# Mid.net
KiCad netlist of a schematic drawn in Altium Designer
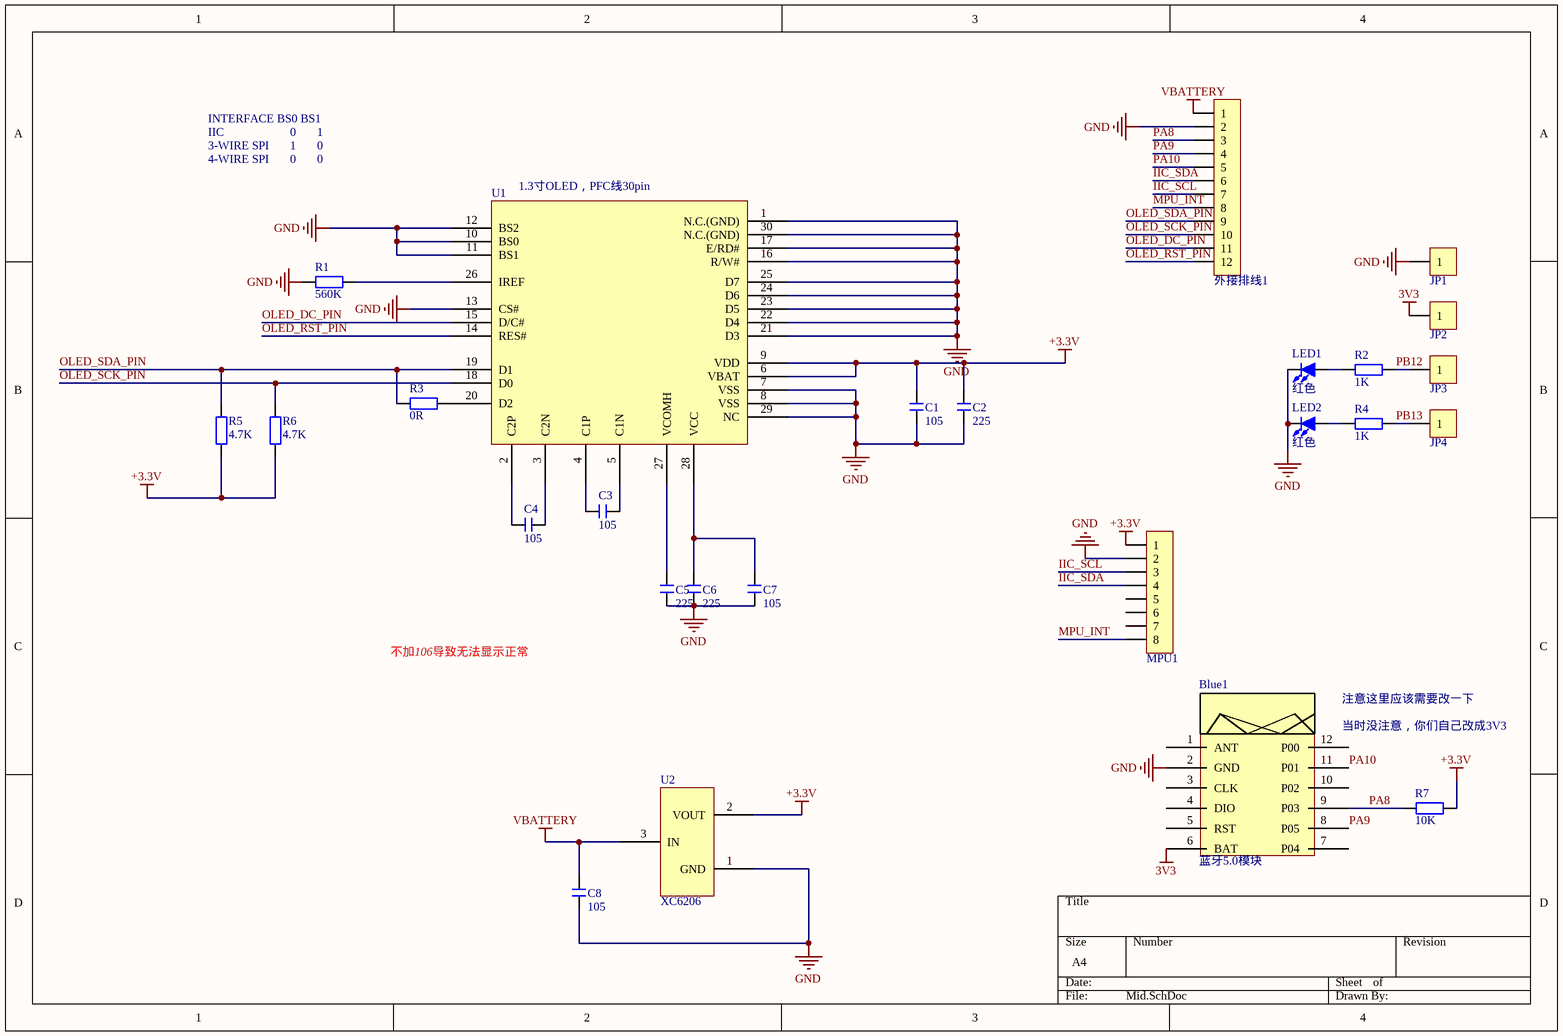
[diagram p0: Mid.SchDoc]

(export (version "E")
  (design (tool "Eeschema 10.0.6"))
  (components
    (comp (ref "Blue1") (value "蓝牙5.0模块") (footprint "PW02") (libsource (lib "未分类器件") (part "PW02")))
    (comp (ref "C1")
      (value "105")
      (footprint "C 0805")
      (description "无极性贴片电容")
      (fields (field (name "版权归属") "源创客"))
      (libsource (lib "电阻-电容-电感") (part "C"))
    )
    (comp (ref "C2")
      (value "225")
      (footprint "C 0805")
      (description "无极性贴片电容")
      (fields (field (name "版权归属") "源创客"))
      (libsource (lib "电阻-电容-电感") (part "C"))
    )
    (comp (ref "C3")
      (value "105")
      (footprint "C 0805")
      (description "无极性贴片电容")
      (fields (field (name "版权归属") "源创客"))
      (libsource (lib "电阻-电容-电感") (part "C"))
    )
    (comp (ref "C4")
      (value "105")
      (footprint "C 0805")
      (description "无极性贴片电容")
      (fields (field (name "版权归属") "源创客"))
      (libsource (lib "电阻-电容-电感") (part "C"))
    )
    (comp (ref "C5")
      (value "225")
      (footprint "C 0805")
      (description "无极性贴片电容")
      (fields (field (name "版权归属") "源创客"))
      (libsource (lib "电阻-电容-电感") (part "C"))
    )
    (comp (ref "C6")
      (value "225")
      (footprint "C 0805")
      (description "无极性贴片电容")
      (fields (field (name "版权归属") "源创客"))
      (libsource (lib "电阻-电容-电感") (part "C"))
    )
    (comp (ref "C7")
      (value "105")
      (footprint "C 0805")
      (description "无极性贴片电容")
      (fields (field (name "版权归属") "源创客"))
      (libsource (lib "电阻-电容-电感") (part "C"))
    )
    (comp (ref "C8")
      (value "105")
      (footprint "C 0805")
      (description "无极性贴片电容")
      (fields (field (name "版权归属") "源创客"))
      (libsource (lib "电阻-电容-电感") (part "C"))
    )
    (comp (ref "JP1")
      (value "HDR-1X1")
      (footprint "HDR-1X1")
      (description "1P接插件")
      (fields (field (name "版权归属") "源创客"))
      (libsource (lib "接插件") (part "Header 1"))
    )
    (comp (ref "JP2")
      (value "HDR-1X1")
      (footprint "HDR-1X1")
      (description "1P接插件")
      (fields (field (name "版权归属") "源创客"))
      (libsource (lib "接插件") (part "Header 1"))
    )
    (comp (ref "JP3")
      (value "HDR-1X1")
      (footprint "HDR-1X1")
      (description "1P接插件")
      (fields (field (name "版权归属") "源创客"))
      (libsource (lib "接插件") (part "Header 1"))
    )
    (comp (ref "JP4")
      (value "HDR-1X1")
      (footprint "HDR-1X1")
      (description "1P接插件")
      (fields (field (name "版权归属") "源创客"))
      (libsource (lib "接插件") (part "Header 1"))
    )
    (comp (ref "LED1")
      (value "红色")
      (footprint "LED 0805B")
      (description "贴片LED")
      (fields (field (name "版权归属") "源创客"))
      (libsource (lib "LED") (part "LED-SMD"))
    )
    (comp (ref "LED2")
      (value "红色")
      (footprint "LED 0805G")
      (description "贴片LED")
      (fields (field (name "版权归属") "源创客"))
      (libsource (lib "LED") (part "LED-SMD"))
    )
    (comp (ref "MPU1")
      (value "HDR-1X8")
      (footprint "HDR-1X8")
      (description "8P接插件")
      (fields (field (name "版权归属") "源创客"))
      (libsource (lib "接插件") (part "Header 8"))
    )
    (comp (ref "R1")
      (value "560K")
      (footprint "R 0805")
      (description "贴片电阻")
      (fields (field (name "版权归属") "源创客"))
      (libsource (lib "电阻-电容-电感") (part "R"))
    )
    (comp (ref "R2")
      (value "1K")
      (footprint "R 0805")
      (description "贴片电阻")
      (fields (field (name "版权归属") "源创客"))
      (libsource (lib "电阻-电容-电感") (part "R"))
    )
    (comp (ref "R3")
      (value "0R")
      (footprint "R 0805")
      (description "贴片电阻")
      (fields (field (name "版权归属") "源创客"))
      (libsource (lib "电阻-电容-电感") (part "R"))
    )
    (comp (ref "R4")
      (value "1K")
      (footprint "R 0805")
      (description "贴片电阻")
      (fields (field (name "版权归属") "源创客"))
      (libsource (lib "电阻-电容-电感") (part "R"))
    )
    (comp (ref "R5")
      (value "4.7K")
      (footprint "R 0805")
      (description "贴片电阻")
      (fields (field (name "版权归属") "源创客"))
      (libsource (lib "电阻-电容-电感") (part "R"))
    )
    (comp (ref "R6")
      (value "4.7K")
      (footprint "R 0805")
      (description "贴片电阻")
      (fields (field (name "版权归属") "源创客"))
      (libsource (lib "电阻-电容-电感") (part "R"))
    )
    (comp (ref "R7")
      (value "10K")
      (footprint "R 0805")
      (description "贴片电阻")
      (fields (field (name "版权归属") "源创客"))
      (libsource (lib "电阻-电容-电感") (part "R"))
    )
    (comp (ref "U1")
      (value "1.3寸OLED，PFC线30pin")
      (footprint "1.3寸OLED-PFC")
      (libsource (lib "我的元件") (part "1.3寸OLED，PFC线30pin"))
    )
    (comp (ref "U2")
      (value "XC6206")
      (footprint "SOT23-3N")
      (description "稳压芯片")
      (libsource (lib "我的元件") (part "XC6206"))
    )
    (comp (ref "外接排线1")
      (value "HDR-1X12")
      (footprint "HDR-1X12")
      (description "12P接插件")
      (fields (field (name "版权归属") "源创客"))
      (libsource (lib "接插件") (part "Header 12"))
    )
  )
  (nets
    (net (code "1") (name "+3.3V") (class "Default")
      (node (ref "C1") (pin "2") (pinfunction "2_2") (pintype "passive"))
      (node (ref "C2") (pin "2") (pinfunction "2_2") (pintype "passive"))
      (node (ref "MPU1") (pin "1") (pinfunction "1_1") (pintype "passive"))
      (node (ref "R5") (pin "2") (pinfunction "2_2") (pintype "passive"))
      (node (ref "R6") (pin "2") (pinfunction "2_2") (pintype "passive"))
      (node (ref "R7") (pin "2") (pinfunction "2_2") (pintype "passive"))
      (node (ref "U1") (pin "6") (pinfunction "VBAT_6") (pintype "passive"))
      (node (ref "U1") (pin "9") (pinfunction "VDD_9") (pintype "passive"))
      (node (ref "U2") (pin "2") (pinfunction "VOUT_2") (pintype "passive"))
    )
    (net (code "2") (name "/IIC_SCL") (class "Default")
      (node (ref "MPU1") (pin "3") (pinfunction "3_3") (pintype "passive"))
      (node (ref "外接排线1") (pin "7") (pinfunction "7_7") (pintype "passive"))
    )
    (net (code "3") (name "/IIC_SDA") (class "Default")
      (node (ref "MPU1") (pin "4") (pinfunction "4_4") (pintype "passive"))
      (node (ref "外接排线1") (pin "6") (pinfunction "6_6") (pintype "passive"))
    )
    (net (code "4") (name "/MPU_INT") (class "Default")
      (node (ref "MPU1") (pin "8") (pinfunction "8_8") (pintype "passive"))
      (node (ref "外接排线1") (pin "8") (pinfunction "8_8") (pintype "passive"))
    )
    (net (code "5") (name "/OLED_DC_PIN") (class "Default")
      (node (ref "U1") (pin "15") (pinfunction "D/C#_15") (pintype "passive"))
      (node (ref "外接排线1") (pin "11") (pinfunction "11_11") (pintype "passive"))
    )
    (net (code "6") (name "/OLED_RST_PIN") (class "Default")
      (node (ref "U1") (pin "14") (pinfunction "RES#_14") (pintype "passive"))
      (node (ref "外接排线1") (pin "12") (pinfunction "12_12") (pintype "passive"))
    )
    (net (code "7") (name "/OLED_SCK_PIN") (class "Default")
      (node (ref "R6") (pin "1") (pinfunction "1_1") (pintype "passive"))
      (node (ref "U1") (pin "18") (pinfunction "D0_18") (pintype "passive"))
      (node (ref "外接排线1") (pin "10") (pinfunction "10_10") (pintype "passive"))
    )
    (net (code "8") (name "/OLED_SDA_PIN") (class "Default")
      (node (ref "R3") (pin "1") (pinfunction "1_1") (pintype "passive"))
      (node (ref "R5") (pin "1") (pinfunction "1_1") (pintype "passive"))
      (node (ref "U1") (pin "19") (pinfunction "D1_19") (pintype "passive"))
      (node (ref "外接排线1") (pin "9") (pinfunction "9_9") (pintype "passive"))
    )
    (net (code "9") (name "/PA8") (class "Default")
      (node (ref "Blue1") (pin "9") (pinfunction "P03_9") (pintype "passive"))
      (node (ref "R7") (pin "1") (pinfunction "1_1") (pintype "passive"))
      (node (ref "外接排线1") (pin "3") (pinfunction "3_3") (pintype "passive"))
    )
    (net (code "10") (name "/PA9") (class "Default")
      (node (ref "Blue1") (pin "8") (pinfunction "P05_8") (pintype "passive"))
      (node (ref "外接排线1") (pin "4") (pinfunction "4_4") (pintype "passive"))
    )
    (net (code "11") (name "/PA10") (class "Default")
      (node (ref "Blue1") (pin "11") (pinfunction "P01_11") (pintype "passive"))
      (node (ref "外接排线1") (pin "5") (pinfunction "5_5") (pintype "passive"))
    )
    (net (code "12") (name "/PB12") (class "Default")
      (node (ref "JP3") (pin "1") (pinfunction "1_1") (pintype "passive"))
      (node (ref "R2") (pin "2") (pinfunction "2_2") (pintype "passive"))
    )
    (net (code "13") (name "/PB13") (class "Default")
      (node (ref "JP4") (pin "1") (pinfunction "1_1") (pintype "passive"))
      (node (ref "R4") (pin "2") (pinfunction "2_2") (pintype "passive"))
    )
    (net (code "14") (name "3V3") (class "Default")
      (node (ref "Blue1") (pin "6") (pinfunction "BAT_6") (pintype "passive"))
      (node (ref "JP2") (pin "1") (pinfunction "1_1") (pintype "passive"))
    )
    (net (code "15") (name "GND") (class "Default")
      (node (ref "Blue1") (pin "2") (pinfunction "GND_2") (pintype "passive"))
      (node (ref "C1") (pin "1") (pinfunction "1_1") (pintype "passive"))
      (node (ref "C2") (pin "1") (pinfunction "1_1") (pintype "passive"))
      (node (ref "C5") (pin "1") (pinfunction "1_1") (pintype "passive"))
      (node (ref "C6") (pin "1") (pinfunction "1_1") (pintype "passive"))
      (node (ref "C7") (pin "1") (pinfunction "1_1") (pintype "passive"))
      (node (ref "C8") (pin "2") (pinfunction "2_2") (pintype "passive"))
      (node (ref "JP1") (pin "1") (pinfunction "1_1") (pintype "passive"))
      (node (ref "LED1") (pin "2") (pinfunction "K_2") (pintype "passive"))
      (node (ref "LED2") (pin "2") (pinfunction "K_2") (pintype "passive"))
      (node (ref "MPU1") (pin "2") (pinfunction "2_2") (pintype "passive"))
      (node (ref "R1") (pin "1") (pinfunction "1_1") (pintype "passive"))
      (node (ref "U1") (pin "1") (pinfunction "N.C.(GND)_1") (pintype "passive"))
      (node (ref "U1") (pin "10") (pinfunction "BS0_10") (pintype "passive"))
      (node (ref "U1") (pin "11") (pinfunction "BS1_11") (pintype "passive"))
      (node (ref "U1") (pin "12") (pinfunction "BS2_12") (pintype "passive"))
      (node (ref "U1") (pin "13") (pinfunction "CS#_13") (pintype "passive"))
      (node (ref "U1") (pin "16") (pinfunction "R/W#_16") (pintype "passive"))
      (node (ref "U1") (pin "17") (pinfunction "E/RD#_17") (pintype "passive"))
      (node (ref "U1") (pin "21") (pinfunction "D3_21") (pintype "passive"))
      (node (ref "U1") (pin "22") (pinfunction "D4_22") (pintype "passive"))
      (node (ref "U1") (pin "23") (pinfunction "D5_23") (pintype "passive"))
      (node (ref "U1") (pin "24") (pinfunction "D6_24") (pintype "passive"))
      (node (ref "U1") (pin "25") (pinfunction "D7_25") (pintype "passive"))
      (node (ref "U1") (pin "29") (pinfunction "NC_29") (pintype "passive"))
      (node (ref "U1") (pin "30") (pinfunction "N.C.(GND)_30") (pintype "passive"))
      (node (ref "U1") (pin "7") (pinfunction "VSS_7") (pintype "passive"))
      (node (ref "U1") (pin "8") (pinfunction "VSS_8") (pintype "passive"))
      (node (ref "U2") (pin "1") (pinfunction "GND_1") (pintype "passive"))
      (node (ref "外接排线1") (pin "2") (pinfunction "2_2") (pintype "passive"))
    )
    (net (code "16") (name "Net-(LED1-A)") (class "Default")
      (node (ref "LED1") (pin "1") (pinfunction "A_1") (pintype "passive"))
      (node (ref "R2") (pin "1") (pinfunction "1_1") (pintype "passive"))
    )
    (net (code "17") (name "Net-(LED2-A)") (class "Default")
      (node (ref "LED2") (pin "1") (pinfunction "A_1") (pintype "passive"))
      (node (ref "R4") (pin "1") (pinfunction "1_1") (pintype "passive"))
    )
    (net (code "18") (name "Net-(U1-C1N)") (class "Default")
      (node (ref "C3") (pin "1") (pinfunction "1_1") (pintype "passive"))
      (node (ref "U1") (pin "5") (pinfunction "C1N_5") (pintype "passive"))
    )
    (net (code "19") (name "Net-(U1-C1P)") (class "Default")
      (node (ref "C3") (pin "2") (pinfunction "2_2") (pintype "passive"))
      (node (ref "U1") (pin "4") (pinfunction "C1P_4") (pintype "passive"))
    )
    (net (code "20") (name "Net-(U1-C2N)") (class "Default")
      (node (ref "C4") (pin "1") (pinfunction "1_1") (pintype "passive"))
      (node (ref "U1") (pin "3") (pinfunction "C2N_3") (pintype "passive"))
    )
    (net (code "21") (name "Net-(U1-C2P)") (class "Default")
      (node (ref "C4") (pin "2") (pinfunction "2_2") (pintype "passive"))
      (node (ref "U1") (pin "2") (pinfunction "C2P_2") (pintype "passive"))
    )
    (net (code "22") (name "Net-(U1-D2)") (class "Default")
      (node (ref "R3") (pin "2") (pinfunction "2_2") (pintype "passive"))
      (node (ref "U1") (pin "20") (pinfunction "D2_20") (pintype "passive"))
    )
    (net (code "23") (name "Net-(U1-IREF)") (class "Default")
      (node (ref "R1") (pin "2") (pinfunction "2_2") (pintype "passive"))
      (node (ref "U1") (pin "26") (pinfunction "IREF_26") (pintype "passive"))
    )
    (net (code "24") (name "Net-(U1-VCC)") (class "Default")
      (node (ref "C6") (pin "2") (pinfunction "2_2") (pintype "passive"))
      (node (ref "C7") (pin "2") (pinfunction "2_2") (pintype "passive"))
      (node (ref "U1") (pin "28") (pinfunction "VCC_28") (pintype "passive"))
    )
    (net (code "25") (name "Net-(U1-VCOMH)") (class "Default")
      (node (ref "C5") (pin "2") (pinfunction "2_2") (pintype "passive"))
      (node (ref "U1") (pin "27") (pinfunction "VCOMH_27") (pintype "passive"))
    )
    (net (code "26") (name "VBATTERY") (class "Default")
      (node (ref "C8") (pin "1") (pinfunction "1_1") (pintype "passive"))
      (node (ref "U2") (pin "3") (pinfunction "IN_3") (pintype "passive"))
      (node (ref "外接排线1") (pin "1") (pinfunction "1_1") (pintype "passive"))
    )
    (net (code "27") (name "unconnected-(Blue1-ANT-Pad1)") (class "Default")
      (node (ref "Blue1") (pin "1") (pinfunction "ANT_1") (pintype "passive"))
    )
    (net (code "28") (name "unconnected-(Blue1-CLK-Pad3)") (class "Default")
      (node (ref "Blue1") (pin "3") (pinfunction "CLK_3") (pintype "passive"))
    )
    (net (code "29") (name "unconnected-(Blue1-DIO-Pad4)") (class "Default")
      (node (ref "Blue1") (pin "4") (pinfunction "DIO_4") (pintype "passive"))
    )
    (net (code "30") (name "unconnected-(Blue1-P00-Pad12)") (class "Default")
      (node (ref "Blue1") (pin "12") (pinfunction "P00_12") (pintype "passive"))
    )
    (net (code "31") (name "unconnected-(Blue1-P02-Pad10)") (class "Default")
      (node (ref "Blue1") (pin "10") (pinfunction "P02_10") (pintype "passive"))
    )
    (net (code "32") (name "unconnected-(Blue1-P04-Pad7)") (class "Default")
      (node (ref "Blue1") (pin "7") (pinfunction "P04_7") (pintype "passive"))
    )
    (net (code "33") (name "unconnected-(Blue1-RST-Pad5)") (class "Default")
      (node (ref "Blue1") (pin "5") (pinfunction "RST_5") (pintype "passive"))
    )
    (net (code "34") (name "unconnected-(MPU1-Pad5)") (class "Default")
      (node (ref "MPU1") (pin "5") (pinfunction "5_5") (pintype "passive"))
    )
    (net (code "35") (name "unconnected-(MPU1-Pad6)") (class "Default")
      (node (ref "MPU1") (pin "6") (pinfunction "6_6") (pintype "passive"))
    )
    (net (code "36") (name "unconnected-(MPU1-Pad7)") (class "Default")
      (node (ref "MPU1") (pin "7") (pinfunction "7_7") (pintype "passive"))
    )
  )
)
